# scheme.net
KiCad netlist of a schematic drawn in Altium Designer
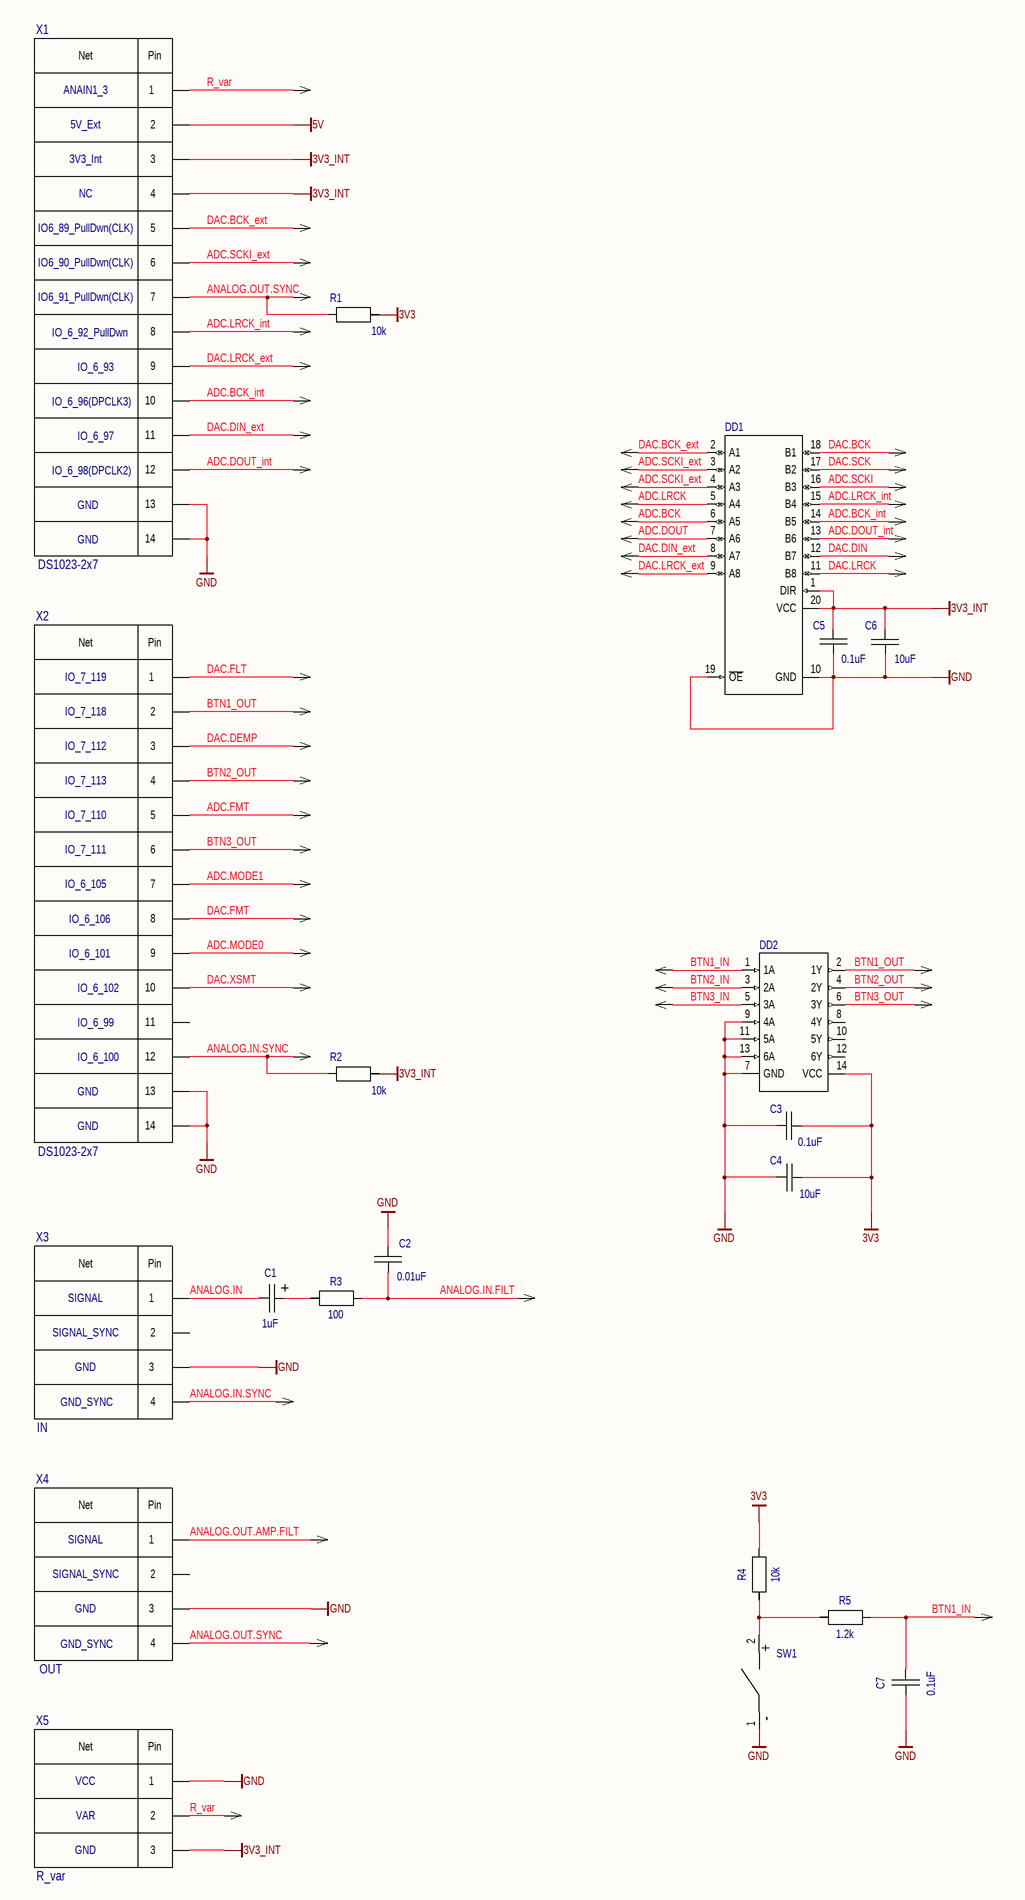
[diagram p0: scheme.SchDoc, left]
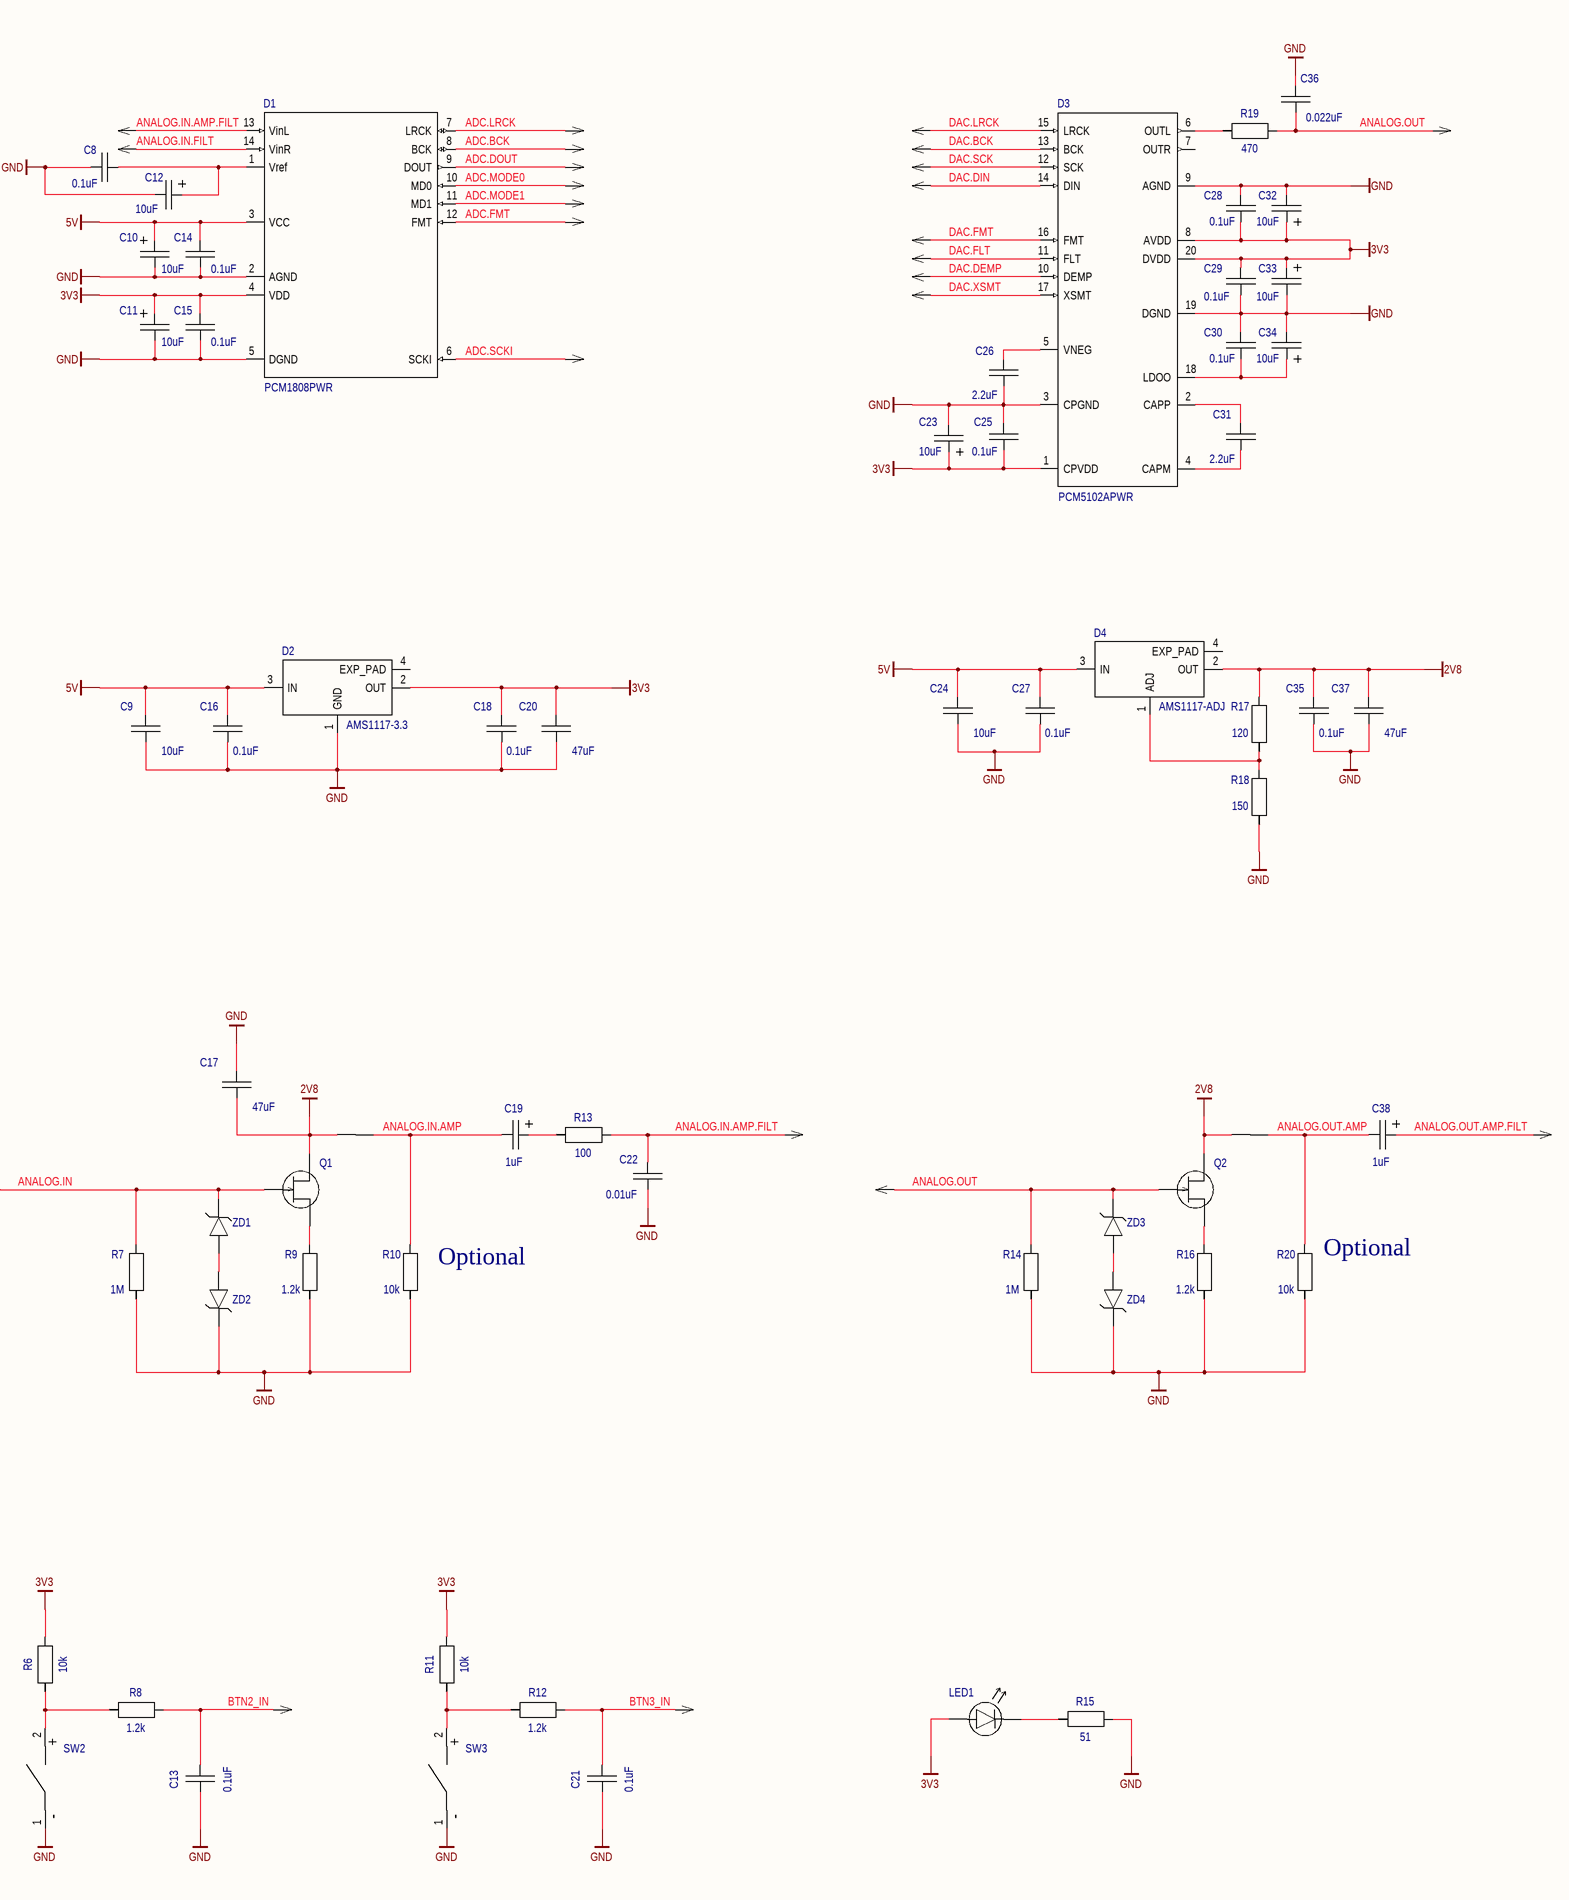
[diagram p1: scheme.SchDoc, right]

(export (version "E")
  (design (tool "Eeschema 10.0.6"))
  (components
    (comp (ref "C1")
      (value "1uF")
      (footprint "SMD_CAP_4x5.4")
      (description "ECAP SMD, 1 uF, 50V, 105°C, 20% 4x5.4mm")
      (libsource (lib "Schlib") (part "JCK1H010M040054"))
    )
    (comp (ref "C2")
      (value "0.01uF")
      (footprint "C0805")
      (description "0.01 uF NPO 50V 5% 0805")
      (libsource (lib "Schlib") (part "GRM2195C1H103J"))
    )
    (comp (ref "C3")
      (value "0.1uF")
      (footprint "C1206")
      (description "SMD 0.1 uF X7R 10%100V 1206")
      (libsource (lib "Schlib") (part "GRM319R72A104KA01D"))
    )
    (comp (ref "C4")
      (value "10uF")
      (footprint "C1206")
      (description "SMD 10 uF X7R 10% 25V 1206")
      (libsource (lib "Schlib") (part "GRM31CR71E106KA12L*"))
    )
    (comp (ref "C5")
      (value "0.1uF")
      (footprint "C1206")
      (description "SMD 0.1 uF X7R 10%100V 1206")
      (libsource (lib "Schlib") (part "GRM319R72A104KA01D"))
    )
    (comp (ref "C6")
      (value "10uF")
      (footprint "C1206")
      (description "SMD 10 uF X7R 10% 25V 1206")
      (libsource (lib "Schlib") (part "GRM31CR71E106KA12L*"))
    )
    (comp (ref "C7")
      (value "0.1uF")
      (footprint "C1206")
      (description "SMD 0.1 uF X7R 10%100V 1206")
      (libsource (lib "Schlib") (part "GRM319R72A104KA01D"))
    )
    (comp (ref "C8")
      (value "0.1uF")
      (footprint "C1206")
      (description "SMD 0.1 uF X7R 10%100V 1206")
      (libsource (lib "Schlib") (part "GRM319R72A104KA01D"))
    )
    (comp (ref "C9")
      (value "10uF")
      (footprint "C1206")
      (description "SMD 10 uF X7R 10% 25V 1206")
      (libsource (lib "Schlib") (part "GRM31CR71E106KA12L*"))
    )
    (comp (ref "C10")
      (value "10uF")
      (footprint "SMD_CAP_4x5.4")
      (description "ECAP SMD, 10uF, 25 V, 105°C, 20% 4x5.4mm")
      (libsource (lib "Schlib") (part "JCK1E100M040054"))
    )
    (comp (ref "C11")
      (value "10uF")
      (footprint "SMD_CAP_4x5.4")
      (description "ECAP SMD, 10uF, 25 V, 105°C, 20% 4x5.4mm")
      (libsource (lib "Schlib") (part "JCK1E100M040054"))
    )
    (comp (ref "C12")
      (value "10uF")
      (footprint "SMD_CAP_4x5.4")
      (description "ECAP SMD, 10uF, 25 V, 105°C, 20% 4x5.4mm")
      (libsource (lib "Schlib") (part "JCK1E100M040054"))
    )
    (comp (ref "C13")
      (value "0.1uF")
      (footprint "C1206")
      (description "SMD 0.1 uF X7R 10%100V 1206")
      (libsource (lib "Schlib") (part "GRM319R72A104KA01D"))
    )
    (comp (ref "C14")
      (value "0.1uF")
      (footprint "C1206")
      (description "SMD 0.1 uF X7R 10%100V 1206")
      (libsource (lib "Schlib") (part "GRM319R72A104KA01D"))
    )
    (comp (ref "C15")
      (value "0.1uF")
      (footprint "C1206")
      (description "SMD 0.1 uF X7R 10%100V 1206")
      (libsource (lib "Schlib") (part "GRM319R72A104KA01D"))
    )
    (comp (ref "C16")
      (value "0.1uF")
      (footprint "C1206")
      (description "SMD 0.1 uF X7R 10%100V 1206")
      (libsource (lib "Schlib") (part "GRM319R72A104KA01D"))
    )
    (comp (ref "C17")
      (value "47uF")
      (footprint "C1210")
      (description "SMD 1210 X5R 47uF 16V 10%")
      (libsource (lib "Schlib") (part "GRM32ER61C476KE15K"))
    )
    (comp (ref "C18")
      (value "0.1uF")
      (footprint "C1206")
      (description "SMD 0.1 uF X7R 10%100V 1206")
      (libsource (lib "Schlib") (part "GRM319R72A104KA01D"))
    )
    (comp (ref "C19")
      (value "1uF")
      (footprint "SMD_CAP_4x5.4")
      (description "ECAP SMD, 1 uF, 50V, 105°C, 20% 4x5.4mm")
      (libsource (lib "Schlib") (part "JCK1H010M040054"))
    )
    (comp (ref "C20")
      (value "47uF")
      (footprint "C1210")
      (description "SMD 1210 X5R 47uF 16V 10%")
      (libsource (lib "Schlib") (part "GRM32ER61C476KE15K"))
    )
    (comp (ref "C21")
      (value "0.1uF")
      (footprint "C1206")
      (description "SMD 0.1 uF X7R 10%100V 1206")
      (libsource (lib "Schlib") (part "GRM319R72A104KA01D"))
    )
    (comp (ref "C22")
      (value "0.01uF")
      (footprint "C0805")
      (description "0.01 uF NPO 50V 5% 0805")
      (libsource (lib "Schlib") (part "GRM2195C1H103J"))
    )
    (comp (ref "C23")
      (value "10uF")
      (footprint "SMD_CAP_4x5.4")
      (description "ECAP SMD, 10uF, 25 V, 105°C, 20% 4x5.4mm")
      (libsource (lib "Schlib") (part "JCK1E100M040054"))
    )
    (comp (ref "C24")
      (value "10uF")
      (footprint "C1206")
      (description "SMD 10 uF X7R 10% 25V 1206")
      (libsource (lib "Schlib") (part "GRM31CR71E106KA12L*"))
    )
    (comp (ref "C25")
      (value "0.1uF")
      (footprint "C1206")
      (description "SMD 0.1 uF X7R 10%100V 1206")
      (libsource (lib "Schlib") (part "GRM319R72A104KA01D"))
    )
    (comp (ref "C26")
      (value "2.2uF")
      (footprint "C1206")
      (description "SMD 2.2мкФ,X7R 50В, 10%, 1206")
      (libsource (lib "Schlib") (part "GRM31CR71H225KA88**L"))
    )
    (comp (ref "C27")
      (value "0.1uF")
      (footprint "C1206")
      (description "SMD 0.1 uF X7R 10%100V 1206")
      (libsource (lib "Schlib") (part "GRM319R72A104KA01D"))
    )
    (comp (ref "C28")
      (value "0.1uF")
      (footprint "C1206")
      (description "SMD 0.1 uF X7R 10%100V 1206")
      (libsource (lib "Schlib") (part "GRM319R72A104KA01D"))
    )
    (comp (ref "C29")
      (value "0.1uF")
      (footprint "C1206")
      (description "SMD 0.1 uF X7R 10%100V 1206")
      (libsource (lib "Schlib") (part "GRM319R72A104KA01D"))
    )
    (comp (ref "C30")
      (value "0.1uF")
      (footprint "C1206")
      (description "SMD 0.1 uF X7R 10%100V 1206")
      (libsource (lib "Schlib") (part "GRM319R72A104KA01D"))
    )
    (comp (ref "C31")
      (value "2.2uF")
      (footprint "C1206")
      (description "SMD 2.2мкФ,X7R 50В, 10%, 1206")
      (libsource (lib "Schlib") (part "GRM31CR71H225KA88**L"))
    )
    (comp (ref "C32")
      (value "10uF")
      (footprint "SMD_CAP_4x5.4")
      (description "ECAP SMD, 10uF, 25 V, 105°C, 20% 4x5.4mm")
      (libsource (lib "Schlib") (part "JCK1E100M040054"))
    )
    (comp (ref "C33")
      (value "10uF")
      (footprint "SMD_CAP_4x5.4")
      (description "ECAP SMD, 10uF, 25 V, 105°C, 20% 4x5.4mm")
      (libsource (lib "Schlib") (part "JCK1E100M040054"))
    )
    (comp (ref "C34")
      (value "10uF")
      (footprint "SMD_CAP_4x5.4")
      (description "ECAP SMD, 10uF, 25 V, 105°C, 20% 4x5.4mm")
      (libsource (lib "Schlib") (part "JCK1E100M040054"))
    )
    (comp (ref "C35")
      (value "0.1uF")
      (footprint "C1206")
      (description "SMD 0.1 uF X7R 10%100V 1206")
      (libsource (lib "Schlib") (part "GRM319R72A104KA01D"))
    )
    (comp (ref "C36")
      (value "0.022uF")
      (footprint "C1206")
      (description "SMD 0.022uF X7R 50V 10% 1206 (22nF)")
      (libsource (lib "Schlib") (part "GRM319R71H223KA01D"))
    )
    (comp (ref "C37")
      (value "47uF")
      (footprint "C1210")
      (description "SMD 1210 X5R 47uF 16V 10%")
      (libsource (lib "Schlib") (part "GRM32ER61C476KE15K"))
    )
    (comp (ref "C38")
      (value "1uF")
      (footprint "SMD_CAP_4x5.4")
      (description "ECAP SMD, 1 uF, 50V, 105°C, 20% 4x5.4mm")
      (libsource (lib "Schlib") (part "JCK1H010M040054"))
    )
    (comp (ref "D1")
      (value "PCM1808PWR")
      (footprint "TSSOP-14")
      (libsource (lib "Schlib") (part "PCM1808PWR"))
    )
    (comp (ref "D2")
      (value "AMS1117-3.3")
      (footprint "SOT223")
      (libsource (lib "Schlib") (part "AMS1117_3.3"))
    )
    (comp (ref "D3")
      (value "PCM5102APWR")
      (footprint "SSOP-20")
      (libsource (lib "Schlib") (part "PCM5102APWR"))
    )
    (comp (ref "D4")
      (value "AMS1117-ADJ")
      (footprint "SOT223")
      (libsource (lib "Schlib") (part "AMS1117-ADJ"))
    )
    (comp (ref "DD1")
      (value "8-ch transceiver")
      (footprint "SOIC-20")
      (libsource (lib "Schlib") (part "SN74LVC245ADW"))
    )
    (comp (ref "DD2")
      (value "SCHMITT-TRIGGER INVERTER")
      (footprint "SOIC-14")
      (libsource (lib "Schlib") (part "SN74HC14D"))
    )
    (comp (ref "LED1")
      (value "KP-2012SEC")
      (footprint "2.0x1.25mm_SMD_CHIP_LED")
      (libsource (lib "Schlib") (part "KP-2012SEC"))
    )
    (comp (ref "NT1") (value "NetTie") (footprint "0805_NetTie") (libsource (lib "Schlib") (part "NetTie")))
    (comp (ref "NT2") (value "NetTie") (footprint "0805_NetTie") (libsource (lib "Schlib") (part "NetTie")))
    (comp (ref "Q1") (value "J201") (footprint "SOT23") (libsource (lib "Schlib") (part "J201")))
    (comp (ref "Q2") (value "J201") (footprint "SOT23") (libsource (lib "Schlib") (part "J201")))
    (comp (ref "R1") (value "10k") (footprint "R2512") (libsource (lib "Schlib") (part "RC0805FR-0710KL")))
    (comp (ref "R2") (value "10k") (footprint "R2512") (libsource (lib "Schlib") (part "RC0805FR-0710KL")))
    (comp (ref "R3") (value "100") (footprint "R2512") (libsource (lib "Schlib") (part "RC2512JR-07100RL")))
    (comp (ref "R4") (value "10k") (footprint "R2512") (libsource (lib "Schlib") (part "RC0805FR-0710KL")))
    (comp (ref "R5") (value "1.2k") (footprint "R2512") (libsource (lib "Schlib") (part "RC2512FR-071K2L")))
    (comp (ref "R6") (value "10k") (footprint "R2512") (libsource (lib "Schlib") (part "RC0805FR-0710KL")))
    (comp (ref "R7") (value "1M") (footprint "R0805") (libsource (lib "Schlib") (part "RC0805JR-071ML")))
    (comp (ref "R8") (value "1.2k") (footprint "R2512") (libsource (lib "Schlib") (part "RC2512FR-071K2L")))
    (comp (ref "R9") (value "1.2k") (footprint "R2512") (libsource (lib "Schlib") (part "RC2512FR-071K2L")))
    (comp (ref "R10") (value "10k") (footprint "R2512") (libsource (lib "Schlib") (part "RC0805FR-0710KL")))
    (comp (ref "R11") (value "10k") (footprint "R2512") (libsource (lib "Schlib") (part "RC0805FR-0710KL")))
    (comp (ref "R12") (value "1.2k") (footprint "R2512") (libsource (lib "Schlib") (part "RC2512FR-071K2L")))
    (comp (ref "R13") (value "100") (footprint "R2512") (libsource (lib "Schlib") (part "RC2512JR-07100RL")))
    (comp (ref "R14") (value "1M") (footprint "R0805") (libsource (lib "Schlib") (part "RC0805JR-071ML")))
    (comp (ref "R15") (value "51") (footprint "R2512") (libsource (lib "Schlib") (part "RC2512JR-0751RL")))
    (comp (ref "R16") (value "1.2k") (footprint "R2512") (libsource (lib "Schlib") (part "RC2512FR-071K2L")))
    (comp (ref "R17") (value "120") (footprint "R2512") (libsource (lib "Schlib") (part "RC2512FR-07120RL")))
    (comp (ref "R18") (value "150") (footprint "R2512") (libsource (lib "Schlib") (part "RC2512FR-07150RL")))
    (comp (ref "R19") (value "470") (footprint "R2512") (libsource (lib "Schlib") (part "RC2512FR-07470RL")))
    (comp (ref "R20") (value "10k") (footprint "R2512") (libsource (lib "Schlib") (part "RC0805FR-0710KL")))
    (comp (ref "SW1")
      (value "simple_button")
      (footprint "BUTTON_template")
      (libsource (lib "Schlib") (part "simple_button"))
    )
    (comp (ref "SW2")
      (value "simple_button")
      (footprint "BUTTON_template")
      (libsource (lib "Schlib") (part "simple_button"))
    )
    (comp (ref "SW3")
      (value "simple_button")
      (footprint "BUTTON_template")
      (libsource (lib "Schlib") (part "simple_button"))
    )
    (comp (ref "X1")
      (value "DS1023-2x7")
      (footprint "DS1023-2x7")
      (description "PBD-14 (DS1023-2x7)")
      (fields
        (field (name "9") "IO_6_93")
        (field (name "14") "GND")
        (field (name "13") "GND")
        (field (name "12") "IO_6_98(DPCLK2)")
        (field (name "11") "IO_6_97")
        (field (name "10") "IO_6_96(DPCLK3)")
        (field (name "8") "IO_6_92_PullDwn")
        (field (name "1") "ANAIN1_3")
        (field (name "2") "5V_Ext")
        (field (name "3") "3V3_Int")
        (field (name "4") "NC")
        (field (name "5") "IO6_89_PullDwn(CLK)")
        (field (name "6") "IO6_90_PullDwn(CLK)")
        (field (name "7") "IO6_91_PullDwn(CLK)")
      )
      (libsource (lib "Schlib") (part "PBD-14 (DS1023-2x7)"))
    )
    (comp (ref "X2")
      (value "DS1023-2x7")
      (footprint "DS1023-2x7")
      (description "PBD-14 (DS1023-2x7)")
      (fields
        (field (name "9") "IO_6_101")
        (field (name "14") "GND")
        (field (name "13") "GND")
        (field (name "12") "IO_6_100")
        (field (name "11") "IO_6_99")
        (field (name "10") "IO_6_102")
        (field (name "8") "IO_6_106")
        (field (name "1") "IO_7_119")
        (field (name "2") "IO_7_118")
        (field (name "3") "IO_7_112")
        (field (name "4") "IO_7_113")
        (field (name "5") "IO_7_110")
        (field (name "6") "IO_7_111")
        (field (name "7") "IO_6_105")
      )
      (libsource (lib "Schlib") (part "PBD-14 (DS1023-2x7)"))
    )
    (comp (ref "X3")
      (value "IN")
      (footprint "NYS_2152_6.35mm")
      (description "Jack 6.35mm MONO")
      (fields
        (field (name "1") "SIGNAL")
        (field (name "2") "SIGNAL_SYNC")
        (field (name "4") "GND_SYNC")
        (field (name "3") "GND")
      )
      (libsource (lib "Schlib") (part "NYS_2152_6.35mm"))
    )
    (comp (ref "X4")
      (value "OUT")
      (footprint "NYS_2152_6.35mm")
      (description "Jack 6.35mm MONO")
      (fields
        (field (name "1") "SIGNAL")
        (field (name "2") "SIGNAL_SYNC")
        (field (name "4") "GND_SYNC")
        (field (name "3") "GND")
      )
      (libsource (lib "Schlib") (part "NYS_2152_6.35mm"))
    )
    (comp (ref "X5")
      (value "R_var")
      (footprint "PTD90")
      (fields (field (name "1") "VCC") (field (name "2") "VAR") (field (name "3") "GND"))
      (libsource (lib "Schlib") (part "Rvar_blank"))
    )
    (comp (ref "ZD1") (value "1N4733A") (footprint "DO-41") (libsource (lib "Schlib") (part "1N4733A")))
    (comp (ref "ZD2") (value "1N4733A") (footprint "DO-41") (libsource (lib "Schlib") (part "1N4733A")))
    (comp (ref "ZD3") (value "1N4733A") (footprint "DO-41") (libsource (lib "Schlib") (part "1N4733A")))
    (comp (ref "ZD4") (value "1N4733A") (footprint "DO-41") (libsource (lib "Schlib") (part "1N4733A")))
  )
  (nets
    (net (code "1") (name "/ADC.BCK") (class "Default")
      (node (ref "D1") (pin "8") (pinfunction "BCK_8") (pintype "bidirectional"))
      (node (ref "DD1") (pin "6") (pinfunction "A5_6") (pintype "bidirectional"))
    )
    (net (code "2") (name "/ADC.BCK_int") (class "Default")
      (node (ref "DD1") (pin "14") (pinfunction "B5_14") (pintype "bidirectional"))
      (node (ref "X1") (pin "10") (pinfunction "10_10") (pintype "passive"))
    )
    (net (code "3") (name "/ADC.DOUT") (class "Default")
      (node (ref "D1") (pin "9") (pinfunction "DOUT_9") (pintype "output"))
      (node (ref "DD1") (pin "7") (pinfunction "A6_7") (pintype "bidirectional"))
    )
    (net (code "4") (name "/ADC.DOUT_int") (class "Default")
      (node (ref "DD1") (pin "13") (pinfunction "B6_13") (pintype "bidirectional"))
      (node (ref "X1") (pin "12") (pinfunction "12_12") (pintype "passive"))
    )
    (net (code "5") (name "/ADC.FMT") (class "Default")
      (node (ref "D1") (pin "12") (pinfunction "FMT_12") (pintype "input"))
      (node (ref "X2") (pin "5") (pinfunction "5_5") (pintype "passive"))
    )
    (net (code "6") (name "/ADC.LRCK") (class "Default")
      (node (ref "D1") (pin "7") (pinfunction "LRCK_7") (pintype "bidirectional"))
      (node (ref "DD1") (pin "5") (pinfunction "A4_5") (pintype "bidirectional"))
    )
    (net (code "7") (name "/ADC.LRCK_int") (class "Default")
      (node (ref "DD1") (pin "15") (pinfunction "B4_15") (pintype "bidirectional"))
      (node (ref "X1") (pin "8") (pinfunction "8_8") (pintype "passive"))
    )
    (net (code "8") (name "/ADC.MODE0") (class "Default")
      (node (ref "D1") (pin "10") (pinfunction "MD0_10") (pintype "input"))
      (node (ref "X2") (pin "9") (pinfunction "9_9") (pintype "passive"))
    )
    (net (code "9") (name "/ADC.MODE1") (class "Default")
      (node (ref "D1") (pin "11") (pinfunction "MD1_11") (pintype "input"))
      (node (ref "X2") (pin "7") (pinfunction "7_7") (pintype "passive"))
    )
    (net (code "10") (name "/ADC.SCKI") (class "Default")
      (node (ref "D1") (pin "6") (pinfunction "SCKI_6") (pintype "input"))
      (node (ref "DD1") (pin "16") (pinfunction "B3_16") (pintype "bidirectional"))
    )
    (net (code "11") (name "/ADC.SCKI_ext") (class "Default")
      (node (ref "DD1") (pin "3") (pinfunction "A2_3") (pintype "bidirectional"))
      (node (ref "DD1") (pin "4") (pinfunction "A3_4") (pintype "bidirectional"))
      (node (ref "X1") (pin "6") (pinfunction "6_6") (pintype "passive"))
    )
    (net (code "12") (name "/ANALOG.IN") (class "Default")
      (node (ref "C1") (pin "2") (pinfunction "Neg_2") (pintype "passive"))
      (node (ref "Q1") (pin "3") (pinfunction "G_3") (pintype "passive"))
      (node (ref "R7") (pin "2") (pinfunction "2_2") (pintype "passive"))
      (node (ref "X3") (pin "1") (pinfunction "1_1") (pintype "passive"))
      (node (ref "ZD1") (pin "2") (pinfunction "C_2") (pintype "passive"))
    )
    (net (code "13") (name "/ANALOG.IN.AMP") (class "Default")
      (node (ref "C19") (pin "2") (pinfunction "Neg_2") (pintype "passive"))
      (node (ref "NT1") (pin "2") (pintype "passive"))
      (node (ref "R10") (pin "2") (pinfunction "2_2") (pintype "passive"))
    )
    (net (code "14") (name "/ANALOG.IN.AMP.FILT") (class "Default")
      (node (ref "C22") (pin "2") (pinfunction "2_2") (pintype "passive"))
      (node (ref "D1") (pin "13") (pinfunction "VinL_13") (pintype "input"))
      (node (ref "R13") (pin "2") (pinfunction "2_2") (pintype "passive"))
    )
    (net (code "15") (name "/ANALOG.IN.FILT") (class "Default")
      (node (ref "C2") (pin "1") (pinfunction "1_1") (pintype "passive"))
      (node (ref "D1") (pin "14") (pinfunction "VinR_14") (pintype "input"))
      (node (ref "R3") (pin "2") (pinfunction "2_2") (pintype "passive"))
    )
    (net (code "16") (name "/ANALOG.IN.SYNC") (class "Default")
      (node (ref "R2") (pin "2") (pinfunction "2_2") (pintype "passive"))
      (node (ref "X2") (pin "12") (pinfunction "12_12") (pintype "passive"))
      (node (ref "X3") (pin "4") (pinfunction "4_4") (pintype "passive"))
    )
    (net (code "17") (name "/ANALOG.OUT") (class "Default")
      (node (ref "C36") (pin "1") (pinfunction "1_1") (pintype "passive"))
      (node (ref "Q2") (pin "3") (pinfunction "G_3") (pintype "passive"))
      (node (ref "R14") (pin "2") (pinfunction "2_2") (pintype "passive"))
      (node (ref "R19") (pin "2") (pinfunction "2_2") (pintype "passive"))
      (node (ref "ZD3") (pin "2") (pinfunction "C_2") (pintype "passive"))
    )
    (net (code "18") (name "/ANALOG.OUT.AMP") (class "Default")
      (node (ref "C38") (pin "2") (pinfunction "Neg_2") (pintype "passive"))
      (node (ref "NT2") (pin "2") (pintype "passive"))
      (node (ref "R20") (pin "2") (pinfunction "2_2") (pintype "passive"))
    )
    (net (code "19") (name "/ANALOG.OUT.AMP.FILT") (class "Default")
      (node (ref "C38") (pin "1") (pinfunction "Pos_1") (pintype "passive"))
      (node (ref "X4") (pin "1") (pinfunction "1_1") (pintype "passive"))
    )
    (net (code "20") (name "/ANALOG.OUT.SYNC") (class "Default")
      (node (ref "R1") (pin "2") (pinfunction "2_2") (pintype "passive"))
      (node (ref "X1") (pin "7") (pinfunction "7_7") (pintype "passive"))
      (node (ref "X4") (pin "4") (pinfunction "4_4") (pintype "passive"))
    )
    (net (code "21") (name "/BTN1_IN") (class "Default")
      (node (ref "C7") (pin "2") (pinfunction "2_2") (pintype "passive"))
      (node (ref "DD2") (pin "1") (pinfunction "1A_1") (pintype "input"))
      (node (ref "R5") (pin "2") (pinfunction "2_2") (pintype "passive"))
    )
    (net (code "22") (name "/BTN1_OUT") (class "Default")
      (node (ref "DD2") (pin "2") (pinfunction "1Y_2") (pintype "output"))
      (node (ref "X2") (pin "2") (pinfunction "2_2") (pintype "passive"))
    )
    (net (code "23") (name "/BTN2_IN") (class "Default")
      (node (ref "C13") (pin "2") (pinfunction "2_2") (pintype "passive"))
      (node (ref "DD2") (pin "3") (pinfunction "2A_3") (pintype "input"))
      (node (ref "R8") (pin "2") (pinfunction "2_2") (pintype "passive"))
    )
    (net (code "24") (name "/BTN2_OUT") (class "Default")
      (node (ref "DD2") (pin "4") (pinfunction "2Y_4") (pintype "output"))
      (node (ref "X2") (pin "4") (pinfunction "4_4") (pintype "passive"))
    )
    (net (code "25") (name "/BTN3_IN") (class "Default")
      (node (ref "C21") (pin "2") (pinfunction "2_2") (pintype "passive"))
      (node (ref "DD2") (pin "5") (pinfunction "3A_5") (pintype "input"))
      (node (ref "R12") (pin "2") (pinfunction "2_2") (pintype "passive"))
    )
    (net (code "26") (name "/BTN3_OUT") (class "Default")
      (node (ref "DD2") (pin "6") (pinfunction "3Y_6") (pintype "output"))
      (node (ref "X2") (pin "6") (pinfunction "6_6") (pintype "passive"))
    )
    (net (code "27") (name "/DAC.BCK") (class "Default")
      (node (ref "D3") (pin "13") (pinfunction "BCK_13") (pintype "input"))
      (node (ref "DD1") (pin "18") (pinfunction "B1_18") (pintype "bidirectional"))
    )
    (net (code "28") (name "/DAC.BCK_ext") (class "Default")
      (node (ref "DD1") (pin "2") (pinfunction "A1_2") (pintype "bidirectional"))
      (node (ref "X1") (pin "5") (pinfunction "5_5") (pintype "passive"))
    )
    (net (code "29") (name "/DAC.DEMP") (class "Default")
      (node (ref "D3") (pin "10") (pinfunction "DEMP_10") (pintype "input"))
      (node (ref "X2") (pin "3") (pinfunction "3_3") (pintype "passive"))
    )
    (net (code "30") (name "/DAC.DIN") (class "Default")
      (node (ref "D3") (pin "14") (pinfunction "DIN_14") (pintype "input"))
      (node (ref "DD1") (pin "12") (pinfunction "B7_12") (pintype "bidirectional"))
    )
    (net (code "31") (name "/DAC.DIN_ext") (class "Default")
      (node (ref "DD1") (pin "8") (pinfunction "A7_8") (pintype "bidirectional"))
      (node (ref "X1") (pin "11") (pinfunction "11_11") (pintype "passive"))
    )
    (net (code "32") (name "/DAC.FLT") (class "Default")
      (node (ref "D3") (pin "11") (pinfunction "FLT_11") (pintype "input"))
      (node (ref "X2") (pin "1") (pinfunction "1_1") (pintype "passive"))
    )
    (net (code "33") (name "/DAC.FMT") (class "Default")
      (node (ref "D3") (pin "16") (pinfunction "FMT_16") (pintype "input"))
      (node (ref "X2") (pin "8") (pinfunction "8_8") (pintype "passive"))
    )
    (net (code "34") (name "/DAC.LRCK") (class "Default")
      (node (ref "D3") (pin "15") (pinfunction "LRCK_15") (pintype "input"))
      (node (ref "DD1") (pin "11") (pinfunction "B8_11") (pintype "bidirectional"))
    )
    (net (code "35") (name "/DAC.LRCK_ext") (class "Default")
      (node (ref "DD1") (pin "9") (pinfunction "A8_9") (pintype "bidirectional"))
      (node (ref "X1") (pin "9") (pinfunction "9_9") (pintype "passive"))
    )
    (net (code "36") (name "/DAC.SCK") (class "Default")
      (node (ref "D3") (pin "12") (pinfunction "SCK_12") (pintype "input"))
      (node (ref "DD1") (pin "17") (pinfunction "B2_17") (pintype "bidirectional"))
    )
    (net (code "37") (name "/DAC.XSMT") (class "Default")
      (node (ref "D3") (pin "17") (pinfunction "XSMT_17") (pintype "input"))
      (node (ref "X2") (pin "10") (pinfunction "10_10") (pintype "passive"))
    )
    (net (code "38") (name "/R_var") (class "Default")
      (node (ref "X1") (pin "1") (pinfunction "1_1") (pintype "passive"))
      (node (ref "X5") (pin "2") (pinfunction "2_2") (pintype "passive"))
    )
    (net (code "39") (name "2V8") (class "Default")
      (node (ref "C17") (pin "1") (pinfunction "1_1") (pintype "passive"))
      (node (ref "C35") (pin "2") (pinfunction "2_2") (pintype "passive"))
      (node (ref "C37") (pin "2") (pinfunction "2_2") (pintype "passive"))
      (node (ref "D4") (pin "2") (pinfunction "OUT_2") (pintype "power_in"))
      (node (ref "NT1") (pin "1") (pinfunction "*_1") (pintype "passive"))
      (node (ref "NT2") (pin "1") (pinfunction "*_1") (pintype "passive"))
      (node (ref "Q1") (pin "1") (pinfunction "D_1") (pintype "passive"))
      (node (ref "Q2") (pin "1") (pinfunction "D_1") (pintype "passive"))
      (node (ref "R17") (pin "2") (pinfunction "2_2") (pintype "passive"))
    )
    (net (code "40") (name "3V3") (class "Default")
      (node (ref "C11") (pin "1") (pinfunction "Pos_1") (pintype "passive"))
      (node (ref "C15") (pin "2") (pinfunction "2_2") (pintype "passive"))
      (node (ref "C18") (pin "2") (pinfunction "2_2") (pintype "passive"))
      (node (ref "C20") (pin "2") (pinfunction "2_2") (pintype "passive"))
      (node (ref "C23") (pin "1") (pinfunction "Pos_1") (pintype "passive"))
      (node (ref "C25") (pin "1") (pinfunction "1_1") (pintype "passive"))
      (node (ref "C28") (pin "2") (pinfunction "2_2") (pintype "passive"))
      (node (ref "C29") (pin "2") (pinfunction "2_2") (pintype "passive"))
      (node (ref "C3") (pin "2") (pinfunction "2_2") (pintype "passive"))
      (node (ref "C32") (pin "1") (pinfunction "Pos_1") (pintype "passive"))
      (node (ref "C33") (pin "1") (pinfunction "Pos_1") (pintype "passive"))
      (node (ref "C4") (pin "2") (pinfunction "2_2") (pintype "passive"))
      (node (ref "D1") (pin "4") (pinfunction "VDD_4") (pintype "power_in"))
      (node (ref "D2") (pin "2") (pinfunction "OUT_2") (pintype "power_in"))
      (node (ref "D3") (pin "1") (pinfunction "CPVDD_1") (pintype "power_in"))
      (node (ref "D3") (pin "20") (pinfunction "DVDD_20") (pintype "power_in"))
      (node (ref "D3") (pin "8") (pinfunction "AVDD_8") (pintype "power_in"))
      (node (ref "DD2") (pin "14") (pinfunction "VCC_14") (pintype "power_in"))
      (node (ref "LED1") (pin "1") (pinfunction "A_1") (pintype "passive"))
      (node (ref "R1") (pin "1") (pinfunction "1_1") (pintype "passive"))
      (node (ref "R11") (pin "2") (pinfunction "2_2") (pintype "passive"))
      (node (ref "R4") (pin "2") (pinfunction "2_2") (pintype "passive"))
      (node (ref "R6") (pin "2") (pinfunction "2_2") (pintype "passive"))
    )
    (net (code "41") (name "3V3_INT") (class "Default")
      (node (ref "C5") (pin "2") (pinfunction "2_2") (pintype "passive"))
      (node (ref "C6") (pin "2") (pinfunction "2_2") (pintype "passive"))
      (node (ref "DD1") (pin "1") (pinfunction "DIR_1") (pintype "input"))
      (node (ref "DD1") (pin "20") (pinfunction "VCC_20") (pintype "power_in"))
      (node (ref "R2") (pin "1") (pinfunction "1_1") (pintype "passive"))
      (node (ref "X1") (pin "3") (pinfunction "3_3") (pintype "passive"))
      (node (ref "X1") (pin "4") (pinfunction "4_4") (pintype "passive"))
      (node (ref "X5") (pin "3") (pinfunction "3_3") (pintype "passive"))
    )
    (net (code "42") (name "5V") (class "Default")
      (node (ref "C10") (pin "1") (pinfunction "Pos_1") (pintype "passive"))
      (node (ref "C14") (pin "2") (pinfunction "2_2") (pintype "passive"))
      (node (ref "C16") (pin "2") (pinfunction "2_2") (pintype "passive"))
      (node (ref "C24") (pin "2") (pinfunction "2_2") (pintype "passive"))
      (node (ref "C27") (pin "2") (pinfunction "2_2") (pintype "passive"))
      (node (ref "C9") (pin "2") (pinfunction "2_2") (pintype "passive"))
      (node (ref "D1") (pin "3") (pinfunction "VCC_3") (pintype "power_in"))
      (node (ref "D2") (pin "3") (pinfunction "IN_3") (pintype "power_in"))
      (node (ref "D4") (pin "3") (pinfunction "IN_3") (pintype "power_in"))
      (node (ref "X1") (pin "2") (pinfunction "2_2") (pintype "passive"))
    )
    (net (code "43") (name "GND") (class "Default")
      (node (ref "C10") (pin "2") (pinfunction "Neg_2") (pintype "passive"))
      (node (ref "C11") (pin "2") (pinfunction "Neg_2") (pintype "passive"))
      (node (ref "C12") (pin "2") (pinfunction "Neg_2") (pintype "passive"))
      (node (ref "C13") (pin "1") (pinfunction "1_1") (pintype "passive"))
      (node (ref "C14") (pin "1") (pinfunction "1_1") (pintype "passive"))
      (node (ref "C15") (pin "1") (pinfunction "1_1") (pintype "passive"))
      (node (ref "C16") (pin "1") (pinfunction "1_1") (pintype "passive"))
      (node (ref "C17") (pin "2") (pinfunction "2_2") (pintype "passive"))
      (node (ref "C18") (pin "1") (pinfunction "1_1") (pintype "passive"))
      (node (ref "C2") (pin "2") (pinfunction "2_2") (pintype "passive"))
      (node (ref "C20") (pin "1") (pinfunction "1_1") (pintype "passive"))
      (node (ref "C21") (pin "1") (pinfunction "1_1") (pintype "passive"))
      (node (ref "C22") (pin "1") (pinfunction "1_1") (pintype "passive"))
      (node (ref "C23") (pin "2") (pinfunction "Neg_2") (pintype "passive"))
      (node (ref "C24") (pin "1") (pinfunction "1_1") (pintype "passive"))
      (node (ref "C25") (pin "2") (pinfunction "2_2") (pintype "passive"))
      (node (ref "C26") (pin "1") (pinfunction "1_1") (pintype "passive"))
      (node (ref "C27") (pin "1") (pinfunction "1_1") (pintype "passive"))
      (node (ref "C28") (pin "1") (pinfunction "1_1") (pintype "passive"))
      (node (ref "C29") (pin "1") (pinfunction "1_1") (pintype "passive"))
      (node (ref "C3") (pin "1") (pinfunction "1_1") (pintype "passive"))
      (node (ref "C30") (pin "1") (pinfunction "1_1") (pintype "passive"))
      (node (ref "C32") (pin "2") (pinfunction "Neg_2") (pintype "passive"))
      (node (ref "C33") (pin "2") (pinfunction "Neg_2") (pintype "passive"))
      (node (ref "C34") (pin "2") (pinfunction "Neg_2") (pintype "passive"))
      (node (ref "C35") (pin "1") (pinfunction "1_1") (pintype "passive"))
      (node (ref "C36") (pin "2") (pinfunction "2_2") (pintype "passive"))
      (node (ref "C37") (pin "1") (pinfunction "1_1") (pintype "passive"))
      (node (ref "C4") (pin "1") (pinfunction "1_1") (pintype "passive"))
      (node (ref "C5") (pin "1") (pinfunction "1_1") (pintype "passive"))
      (node (ref "C6") (pin "1") (pinfunction "1_1") (pintype "passive"))
      (node (ref "C7") (pin "1") (pinfunction "1_1") (pintype "passive"))
      (node (ref "C8") (pin "1") (pinfunction "1_1") (pintype "passive"))
      (node (ref "C9") (pin "1") (pinfunction "1_1") (pintype "passive"))
      (node (ref "D1") (pin "2") (pinfunction "AGND_2") (pintype "power_in"))
      (node (ref "D1") (pin "5") (pinfunction "DGND_5") (pintype "power_in"))
      (node (ref "D2") (pin "1") (pinfunction "GND_1") (pintype "power_in"))
      (node (ref "D3") (pin "19") (pinfunction "DGND_19") (pintype "power_in"))
      (node (ref "D3") (pin "3") (pinfunction "CPGND_3") (pintype "power_in"))
      (node (ref "D3") (pin "9") (pinfunction "AGND_9") (pintype "power_in"))
      (node (ref "DD1") (pin "10") (pinfunction "GND_10") (pintype "power_in"))
      (node (ref "DD1") (pin "19") (pinfunction "~{OE}_19") (pintype "input"))
      (node (ref "DD2") (pin "11") (pinfunction "5A_11") (pintype "input"))
      (node (ref "DD2") (pin "13") (pinfunction "6A_13") (pintype "input"))
      (node (ref "DD2") (pin "7") (pinfunction "GND_7") (pintype "power_in"))
      (node (ref "DD2") (pin "9") (pinfunction "4A_9") (pintype "input"))
      (node (ref "R10") (pin "1") (pinfunction "1_1") (pintype "passive"))
      (node (ref "R14") (pin "1") (pinfunction "1_1") (pintype "passive"))
      (node (ref "R15") (pin "2") (pinfunction "2_2") (pintype "passive"))
      (node (ref "R16") (pin "1") (pinfunction "1_1") (pintype "passive"))
      (node (ref "R18") (pin "1") (pinfunction "1_1") (pintype "passive"))
      (node (ref "R20") (pin "1") (pinfunction "1_1") (pintype "passive"))
      (node (ref "R7") (pin "1") (pinfunction "1_1") (pintype "passive"))
      (node (ref "R9") (pin "1") (pinfunction "1_1") (pintype "passive"))
      (node (ref "SW1") (pin "1") (pinfunction "1_1") (pintype "passive"))
      (node (ref "SW2") (pin "1") (pinfunction "1_1") (pintype "passive"))
      (node (ref "SW3") (pin "1") (pinfunction "1_1") (pintype "passive"))
      (node (ref "X1") (pin "13") (pinfunction "13_13") (pintype "passive"))
      (node (ref "X1") (pin "14") (pinfunction "14_14") (pintype "passive"))
      (node (ref "X2") (pin "13") (pinfunction "13_13") (pintype "passive"))
      (node (ref "X2") (pin "14") (pinfunction "14_14") (pintype "passive"))
      (node (ref "X3") (pin "3") (pinfunction "3_3") (pintype "passive"))
      (node (ref "X4") (pin "3") (pinfunction "3_3") (pintype "passive"))
      (node (ref "X5") (pin "1") (pinfunction "1_1") (pintype "passive"))
      (node (ref "ZD2") (pin "2") (pinfunction "C_2") (pintype "passive"))
      (node (ref "ZD4") (pin "2") (pinfunction "C_2") (pintype "passive"))
    )
    (net (code "44") (name "Net-(C1-Pos)") (class "Default")
      (node (ref "C1") (pin "1") (pinfunction "Pos_1") (pintype "passive"))
      (node (ref "R3") (pin "1") (pinfunction "1_1") (pintype "passive"))
    )
    (net (code "45") (name "Net-(C12-Pos)") (class "Default")
      (node (ref "C12") (pin "1") (pinfunction "Pos_1") (pintype "passive"))
      (node (ref "C8") (pin "2") (pinfunction "2_2") (pintype "passive"))
      (node (ref "D1") (pin "1") (pinfunction "Vref_1") (pintype "power_in"))
    )
    (net (code "46") (name "Net-(C19-Pos)") (class "Default")
      (node (ref "C19") (pin "1") (pinfunction "Pos_1") (pintype "passive"))
      (node (ref "R13") (pin "1") (pinfunction "1_1") (pintype "passive"))
    )
    (net (code "47") (name "Net-(C34-Pos)") (class "Default")
      (node (ref "C30") (pin "2") (pinfunction "2_2") (pintype "passive"))
      (node (ref "C34") (pin "1") (pinfunction "Pos_1") (pintype "passive"))
      (node (ref "D3") (pin "18") (pinfunction "LDOO_18") (pintype "passive"))
    )
    (net (code "48") (name "Net-(D3-CAPM)") (class "Default")
      (node (ref "C31") (pin "1") (pinfunction "1_1") (pintype "passive"))
      (node (ref "D3") (pin "4") (pinfunction "CAPM_4") (pintype "passive"))
    )
    (net (code "49") (name "Net-(D3-CAPP)") (class "Default")
      (node (ref "C31") (pin "2") (pinfunction "2_2") (pintype "passive"))
      (node (ref "D3") (pin "2") (pinfunction "CAPP_2") (pintype "passive"))
    )
    (net (code "50") (name "Net-(D3-OUTL)") (class "Default")
      (node (ref "D3") (pin "6") (pinfunction "OUTL_6") (pintype "output"))
      (node (ref "R19") (pin "1") (pinfunction "1_1") (pintype "passive"))
    )
    (net (code "51") (name "Net-(D3-VNEG)") (class "Default")
      (node (ref "C26") (pin "2") (pinfunction "2_2") (pintype "passive"))
      (node (ref "D3") (pin "5") (pinfunction "VNEG_5") (pintype "passive"))
    )
    (net (code "52") (name "Net-(D4-ADJ)") (class "Default")
      (node (ref "D4") (pin "1") (pinfunction "ADJ_1") (pintype "power_in"))
      (node (ref "R17") (pin "1") (pinfunction "1_1") (pintype "passive"))
      (node (ref "R18") (pin "2") (pinfunction "2_2") (pintype "passive"))
    )
    (net (code "53") (name "Net-(LED1-C)") (class "Default")
      (node (ref "LED1") (pin "2") (pinfunction "C_2") (pintype "passive"))
      (node (ref "R15") (pin "1") (pinfunction "1_1") (pintype "passive"))
    )
    (net (code "54") (name "Net-(Q1-S)") (class "Default")
      (node (ref "Q1") (pin "2") (pinfunction "S_2") (pintype "passive"))
      (node (ref "R9") (pin "2") (pinfunction "2_2") (pintype "passive"))
    )
    (net (code "55") (name "Net-(Q2-S)") (class "Default")
      (node (ref "Q2") (pin "2") (pinfunction "S_2") (pintype "passive"))
      (node (ref "R16") (pin "2") (pinfunction "2_2") (pintype "passive"))
    )
    (net (code "56") (name "Net-(R4-Pad1)") (class "Default")
      (node (ref "R4") (pin "1") (pinfunction "1_1") (pintype "passive"))
      (node (ref "R5") (pin "1") (pinfunction "1_1") (pintype "passive"))
      (node (ref "SW1") (pin "2") (pinfunction "2_2") (pintype "passive"))
    )
    (net (code "57") (name "Net-(R6-Pad1)") (class "Default")
      (node (ref "R6") (pin "1") (pinfunction "1_1") (pintype "passive"))
      (node (ref "R8") (pin "1") (pinfunction "1_1") (pintype "passive"))
      (node (ref "SW2") (pin "2") (pinfunction "2_2") (pintype "passive"))
    )
    (net (code "58") (name "Net-(R11-Pad1)") (class "Default")
      (node (ref "R11") (pin "1") (pinfunction "1_1") (pintype "passive"))
      (node (ref "R12") (pin "1") (pinfunction "1_1") (pintype "passive"))
      (node (ref "SW3") (pin "2") (pinfunction "2_2") (pintype "passive"))
    )
    (net (code "59") (name "Net-(ZD1-A)") (class "Default")
      (node (ref "ZD1") (pin "1") (pinfunction "A_1") (pintype "passive"))
      (node (ref "ZD2") (pin "1") (pinfunction "A_1") (pintype "passive"))
    )
    (net (code "60") (name "Net-(ZD3-A)") (class "Default")
      (node (ref "ZD3") (pin "1") (pinfunction "A_1") (pintype "passive"))
      (node (ref "ZD4") (pin "1") (pinfunction "A_1") (pintype "passive"))
    )
    (net (code "61") (name "unconnected-(D2-EXP_PAD-Pad4)") (class "Default")
      (node (ref "D2") (pin "4") (pinfunction "EXP_PAD_4") (pintype "passive"))
    )
    (net (code "62") (name "unconnected-(D3-OUTR-Pad7)") (class "Default")
      (node (ref "D3") (pin "7") (pinfunction "OUTR_7") (pintype "output"))
    )
    (net (code "63") (name "unconnected-(D4-EXP_PAD-Pad4)") (class "Default")
      (node (ref "D4") (pin "4") (pinfunction "EXP_PAD_4") (pintype "passive"))
    )
    (net (code "64") (name "unconnected-(DD2-4Y-Pad8)") (class "Default")
      (node (ref "DD2") (pin "8") (pinfunction "4Y_8") (pintype "output"))
    )
    (net (code "65") (name "unconnected-(DD2-5Y-Pad10)") (class "Default")
      (node (ref "DD2") (pin "10") (pinfunction "5Y_10") (pintype "output"))
    )
    (net (code "66") (name "unconnected-(DD2-6Y-Pad12)") (class "Default")
      (node (ref "DD2") (pin "12") (pinfunction "6Y_12") (pintype "output"))
    )
    (net (code "67") (name "unconnected-(X2-Pad11)") (class "Default")
      (node (ref "X2") (pin "11") (pinfunction "11_11") (pintype "passive"))
    )
    (net (code "68") (name "unconnected-(X3-Pad2)") (class "Default")
      (node (ref "X3") (pin "2") (pinfunction "2_2") (pintype "passive"))
    )
    (net (code "69") (name "unconnected-(X4-Pad2)") (class "Default")
      (node (ref "X4") (pin "2") (pinfunction "2_2") (pintype "passive"))
    )
  )
)
